# Main_Board_v3_Quad_MD.net
KiCad netlist of a schematic drawn in EAGLE
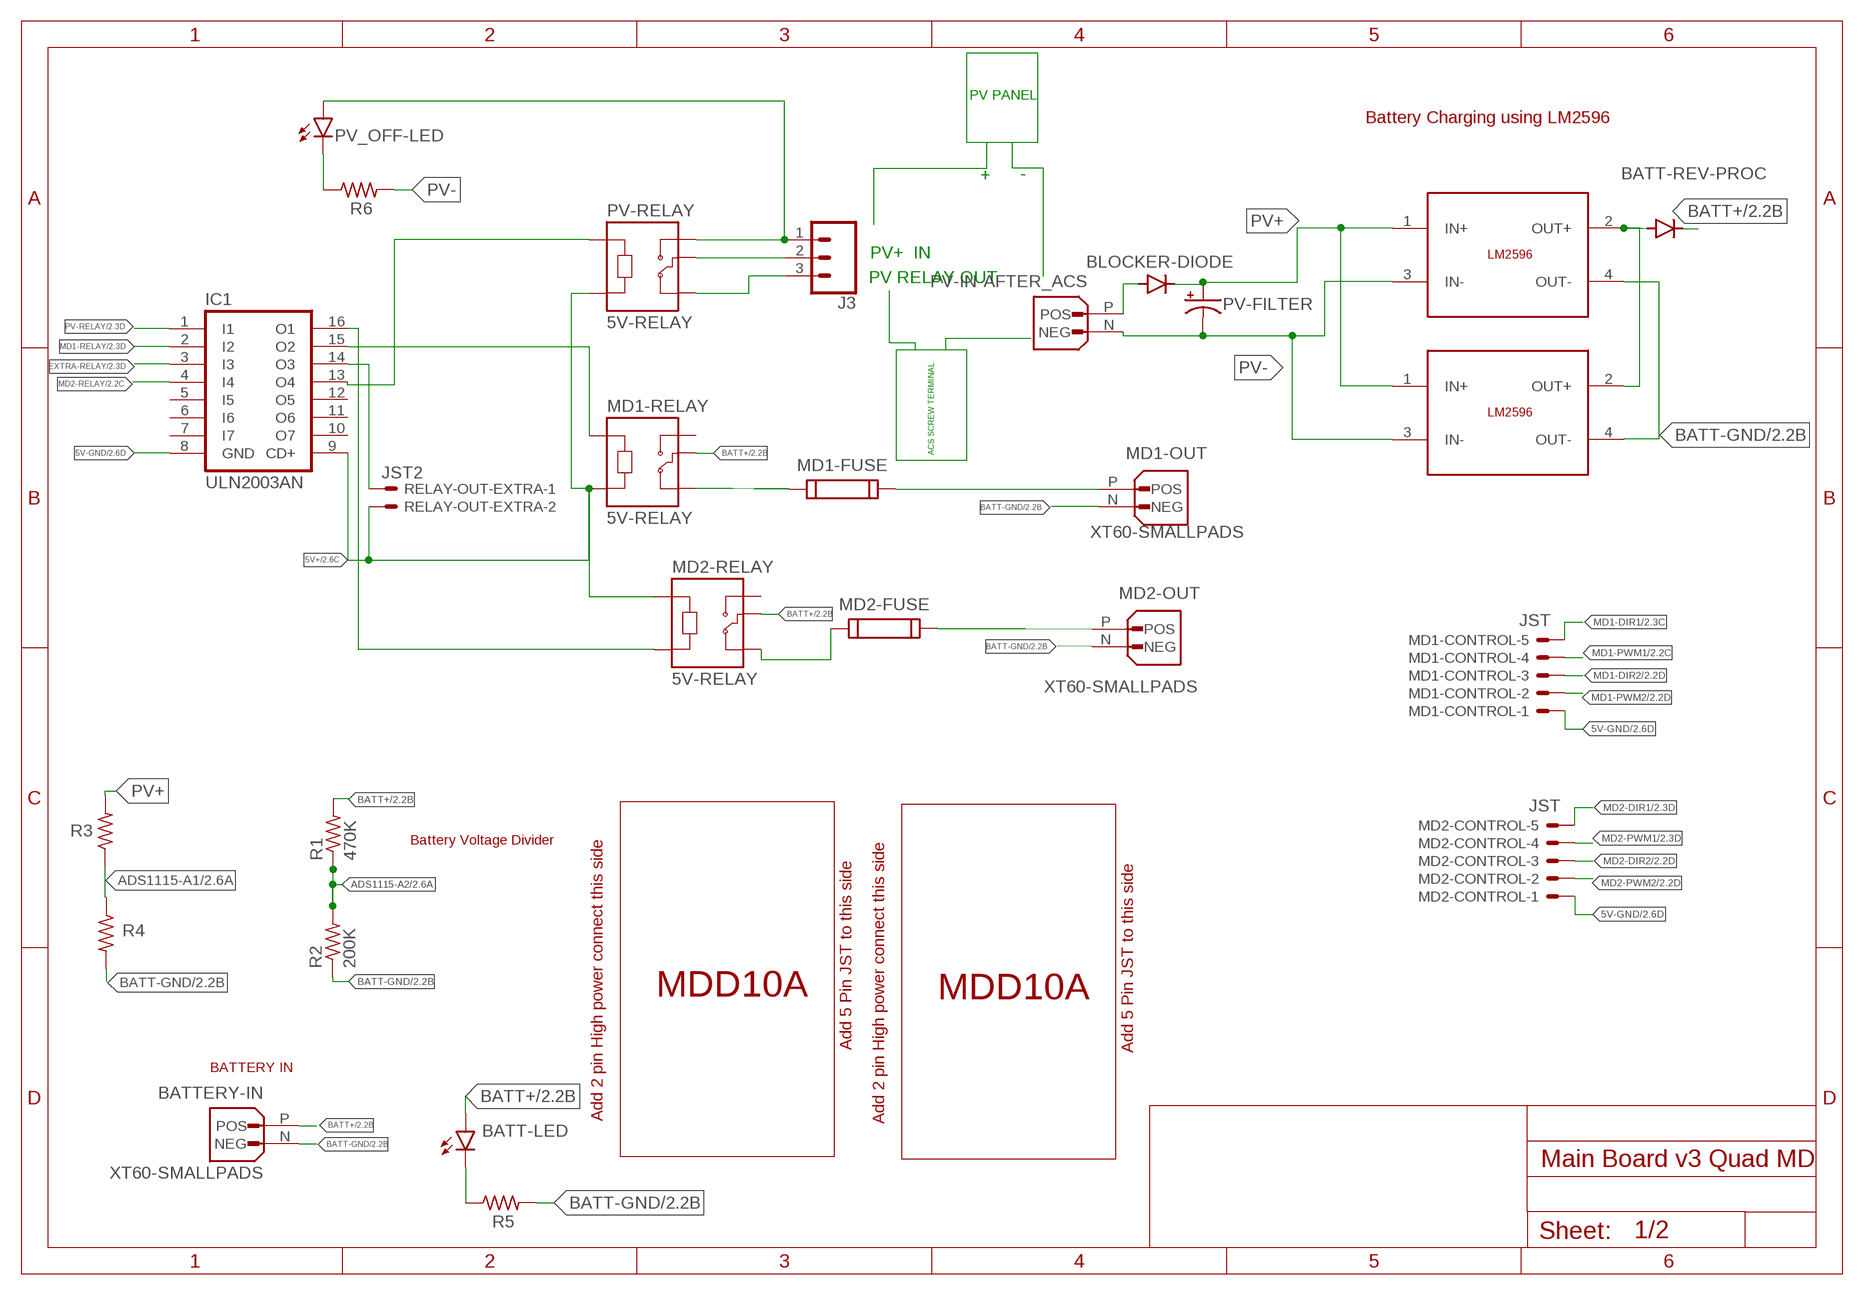
[diagram p0: schematic, sheet 1]
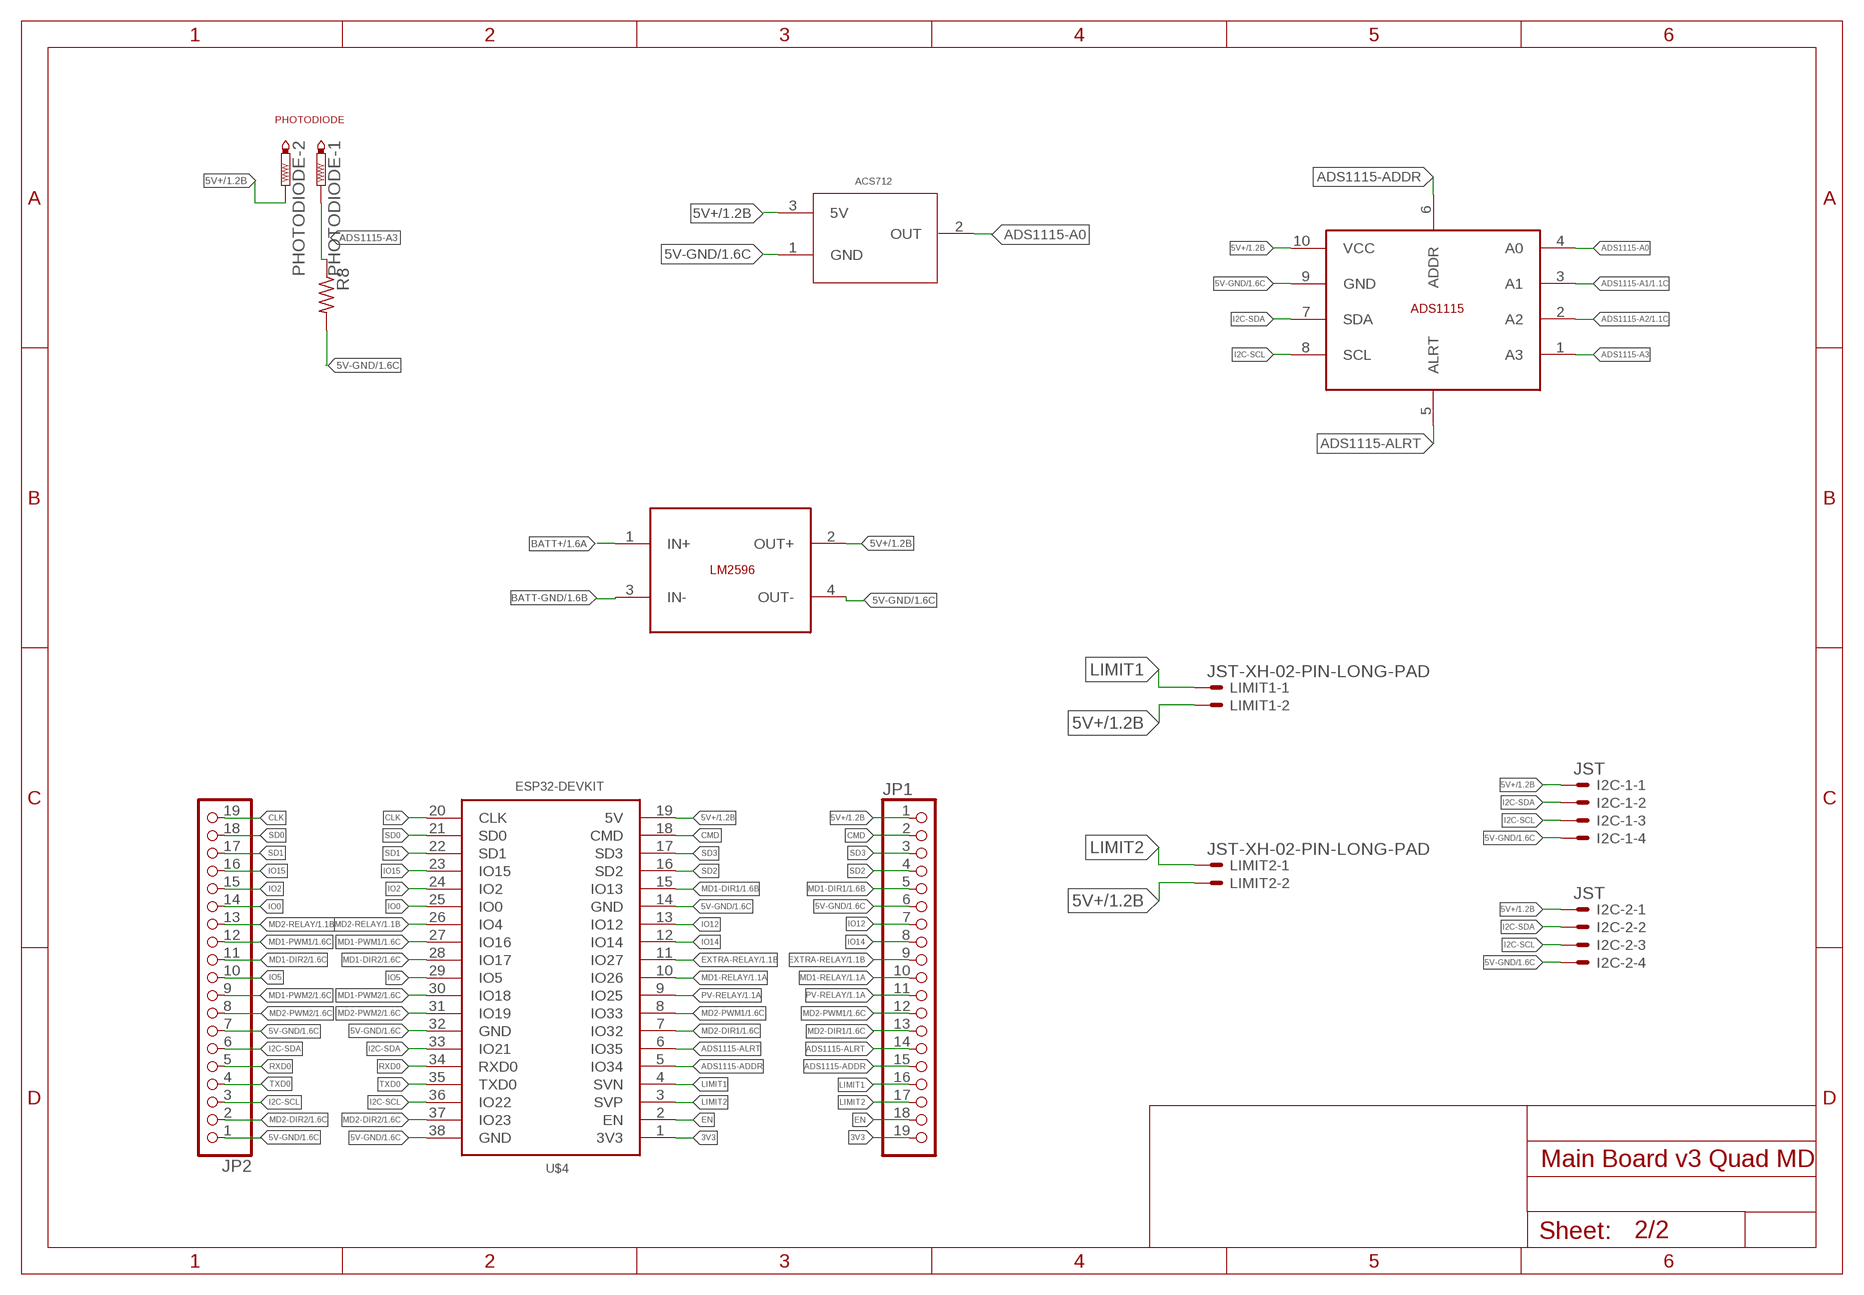
[diagram p1: schematic, sheet 2]

(export (version "E")
  (design (tool "Eeschema 10.0.6"))
  (components
    (comp (ref "BATT-LED")
      (value "SFH482")
      (footprint "eagle-import:SFH482")
      (libsource (lib "eagle-import") (part "SFH482"))
    )
    (comp (ref "BATT-REV-PROC")
      (value "1N5400")
      (footprint "eagle-import:DO201-15")
      (libsource (lib "eagle-import") (part "1N5400"))
    )
    (comp (ref "BATTERY-IN")
      (value "XT60-SMALLPADS")
      (footprint "eagle-import:XT-60-SMALLPADS")
      (libsource (lib "eagle-import") (part "XT60-SMALLPADS"))
    )
    (comp (ref "BLOCKER-DIODE")
      (value "1N5400")
      (footprint "eagle-import:DO201-15")
      (libsource (lib "eagle-import") (part "1N5400"))
    )
    (comp (ref "IC1")
      (value "ULN2003AN")
      (footprint "eagle-import:DIL16")
      (fields
        (field (name "MF") "STMicroelectronics")
        (field (name "MP") "ULN2003A")
        (field (name "SPICEPREFIX") "X")
      )
      (libsource (lib "eagle-import") (part "ULN2003AN"))
    )
    (comp (ref "J3")
      (value "CONN_03SCREW_LOCK")
      (footprint "eagle-import:SCREWTERMINAL-3.5MM-3_LOCK.007S")
      (libsource (lib "eagle-import") (part "CONN_03SCREW_LOCK"))
    )
    (comp (ref "MD1-CONTROL")
      (value "JST")
      (footprint "eagle-import:JST-XH-05-PACKAGE-LONG-PAD")
      (libsource (lib "eagle-import") (part "JST-XH-05-PIN-LONG-PAD"))
    )
    (comp (ref "MD1-FUSE")
      (value "696101000002")
      (footprint "eagle-import:696101000002")
      (libsource (lib "eagle-import") (part "696101000002"))
    )
    (comp (ref "MD1-OUT")
      (value "XT60-SMALLPADS")
      (footprint "eagle-import:XT-60-SMALLPADS")
      (libsource (lib "eagle-import") (part "XT60-SMALLPADS"))
    )
    (comp (ref "MD1-RELAY")
      (value "5V-RELAY")
      (footprint "eagle-import:RELAY-SRD-05VDC-SL-C")
      (fields (field (name "MF") "Songle Relay") (field (name "MP") "SRD-05VDC-SL-C"))
      (libsource (lib "eagle-import") (part "5V-RELAY"))
    )
    (comp (ref "MD2-CONTROL")
      (value "JST")
      (footprint "eagle-import:JST-XH-05-PACKAGE-LONG-PAD")
      (libsource (lib "eagle-import") (part "JST-XH-05-PIN-LONG-PAD"))
    )
    (comp (ref "MD2-FUSE")
      (value "696101000002")
      (footprint "eagle-import:696101000002")
      (libsource (lib "eagle-import") (part "696101000002"))
    )
    (comp (ref "MD2-OUT")
      (value "XT60-SMALLPADS")
      (footprint "eagle-import:XT-60-SMALLPADS")
      (libsource (lib "eagle-import") (part "XT60-SMALLPADS"))
    )
    (comp (ref "MD2-RELAY")
      (value "5V-RELAY")
      (footprint "eagle-import:RELAY-SRD-05VDC-SL-C")
      (fields (field (name "MF") "Songle Relay") (field (name "MP") "SRD-05VDC-SL-C"))
      (libsource (lib "eagle-import") (part "5V-RELAY"))
    )
    (comp (ref "PV-FILTER")
      (value "CPOL-USE5-6")
      (footprint "eagle-import:E5-6")
      (libsource (lib "eagle-import") (part "CPOL-USE5-6"))
    )
    (comp (ref "PV-IN-AFTER_ACS")
      (value "XT60-SMALLPADS")
      (footprint "eagle-import:XT-60-SMALLPADS")
      (libsource (lib "eagle-import") (part "XT60-SMALLPADS"))
    )
    (comp (ref "PV-RELAY")
      (value "5V-RELAY")
      (footprint "eagle-import:RELAY-SRD-05VDC-SL-C")
      (fields (field (name "MF") "Songle Relay") (field (name "MP") "SRD-05VDC-SL-C"))
      (libsource (lib "eagle-import") (part "5V-RELAY"))
    )
    (comp (ref "PV_OFF-LED")
      (value "SFH482")
      (footprint "eagle-import:SFH482")
      (libsource (lib "eagle-import") (part "SFH482"))
    )
    (comp (ref "R1")
      (value "470K")
      (footprint "eagle-import:0309_12")
      (libsource (lib "eagle-import") (part "R-US_0309/12"))
    )
    (comp (ref "R2")
      (value "200K")
      (footprint "eagle-import:0309_12")
      (libsource (lib "eagle-import") (part "R-US_0309/12"))
    )
    (comp (ref "R3")
      (value "R-US_0309/12")
      (footprint "eagle-import:0309_12")
      (libsource (lib "eagle-import") (part "R-US_0309/12"))
    )
    (comp (ref "R4")
      (value "R-US_0309/12")
      (footprint "eagle-import:0309_12")
      (libsource (lib "eagle-import") (part "R-US_0309/12"))
    )
    (comp (ref "R5")
      (value "R-US_0309/12")
      (footprint "eagle-import:0309_12")
      (libsource (lib "eagle-import") (part "R-US_0309/12"))
    )
    (comp (ref "R6")
      (value "R-US_0309/12")
      (footprint "eagle-import:0309_12")
      (libsource (lib "eagle-import") (part "R-US_0309/12"))
    )
    (comp (ref "RELAY-OUT-EXTRA")
      (value "JST2")
      (footprint "eagle-import:JST-XH-02-PACKAGE-LONG-PAD")
      (libsource (lib "eagle-import") (part "JST-XH-02-PIN-LONG-PAD"))
    )
    (comp (ref "U$1")
      (value "LM2596-MODULE")
      (footprint "eagle-import:LM2596-MODULE")
      (libsource (lib "eagle-import") (part "LM2596-MODULE"))
    )
    (comp (ref "U$2")
      (value "LM2596-MODULE")
      (footprint "eagle-import:LM2596-MODULE")
      (libsource (lib "eagle-import") (part "LM2596-MODULE"))
    )
    (comp (ref "U$3")
      (value "MDD10A-MODULE")
      (footprint "eagle-import:MDD10A")
      (libsource (lib "eagle-import") (part "MDD10A-MODULE"))
    )
    (comp (ref "U$7")
      (value "MDD10A-MODULE")
      (footprint "eagle-import:MDD10A")
      (libsource (lib "eagle-import") (part "MDD10A-MODULE"))
    )
    (comp (ref "I2C-1")
      (value "JST")
      (footprint "eagle-import:JST-XH-04-PACKAGE-LONG-PAD")
      (libsource (lib "eagle-import") (part "JST-XH-04-PIN-LONG-PAD"))
    )
    (comp (ref "I2C-2")
      (value "JST")
      (footprint "eagle-import:JST-XH-04-PACKAGE-LONG-PAD")
      (libsource (lib "eagle-import") (part "JST-XH-04-PIN-LONG-PAD"))
    )
    (comp (ref "JP1")
      (value "PINHD-1X19")
      (footprint "eagle-import:1X19")
      (libsource (lib "eagle-import") (part "PINHD-1X19"))
    )
    (comp (ref "JP2")
      (value "PINHD-1X19")
      (footprint "eagle-import:1X19")
      (libsource (lib "eagle-import") (part "PINHD-1X19"))
    )
    (comp (ref "LIMIT1")
      (value "JST-XH-02-PIN-LONG-PAD")
      (footprint "eagle-import:JST-XH-02-PACKAGE-LONG-PAD")
      (libsource (lib "eagle-import") (part "JST-XH-02-PIN-LONG-PAD"))
    )
    (comp (ref "LIMIT2")
      (value "JST-XH-02-PIN-LONG-PAD")
      (footprint "eagle-import:JST-XH-02-PACKAGE-LONG-PAD")
      (libsource (lib "eagle-import") (part "JST-XH-02-PIN-LONG-PAD"))
    )
    (comp (ref "PHOTODIODE")
      (value "PTR2")
      (footprint "eagle-import:P2-38-17")
      (libsource (lib "eagle-import") (part "PTR2"))
    )
    (comp (ref "R8")
      (value "R-US_0309/12")
      (footprint "eagle-import:0309_12")
      (libsource (lib "eagle-import") (part "R-US_0309/12"))
    )
    (comp (ref "U$4")
      (value "ESP32-DEVKIT")
      (footprint "eagle-import:ESP32-38PINS")
      (libsource (lib "eagle-import") (part "ESP32-DEVKIT"))
    )
    (comp (ref "U$5")
      (value "ACS712-MODULE")
      (footprint "eagle-import:ACS712-MODULE")
      (libsource (lib "eagle-import") (part "ACS712-MODULE"))
    )
    (comp (ref "U$6")
      (value "ADS1115-MODULE")
      (footprint "eagle-import:ADS1115-MODULE")
      (libsource (lib "eagle-import") (part "ADS1115-MODULE"))
    )
    (comp (ref "U$8")
      (value "LM2596-MODULE")
      (footprint "eagle-import:LM2596-MODULE")
      (libsource (lib "eagle-import") (part "LM2596-MODULE"))
    )
  )
  (nets
    (net (code "1") (name "3V3") (class "Default")
      (node (ref "JP1") (pin "19") (pinfunction "19_19") (pintype "passive"))
      (node (ref "U$4") (pin "1") (pinfunction "3V3_1") (pintype "bidirectional"))
    )
    (net (code "2") (name "5V+") (class "Default")
      (node (ref "I2C-1") (pin "1") (pinfunction "S_1") (pintype "passive"))
      (node (ref "I2C-2") (pin "1") (pinfunction "S_1") (pintype "passive"))
      (node (ref "IC1") (pin "9") (pinfunction "CD+_9") (pintype "passive"))
      (node (ref "JP1") (pin "1") (pinfunction "1_1") (pintype "passive"))
      (node (ref "LIMIT1") (pin "2") (pinfunction "S_2") (pintype "passive"))
      (node (ref "LIMIT2") (pin "2") (pinfunction "S_2") (pintype "passive"))
      (node (ref "MD1-RELAY") (pin "A2") (pinfunction "A2_A2") (pintype "passive"))
      (node (ref "MD2-RELAY") (pin "A1") (pinfunction "A1_A1") (pintype "passive"))
      (node (ref "PHOTODIODE") (pin "TP-2") (pinfunction "TP_TP-2") (pintype "input"))
      (node (ref "PV-RELAY") (pin "A2") (pinfunction "A2_A2") (pintype "passive"))
      (node (ref "RELAY-OUT-EXTRA") (pin "2") (pinfunction "S_2") (pintype "passive"))
      (node (ref "U$4") (pin "19") (pinfunction "5V_19") (pintype "bidirectional"))
      (node (ref "U$5") (pin "3") (pinfunction "5V_3") (pintype "bidirectional"))
      (node (ref "U$6") (pin "10") (pinfunction "VCC_10") (pintype "bidirectional"))
      (node (ref "U$8") (pin "2") (pinfunction "OUT+_2") (pintype "bidirectional"))
    )
    (net (code "3") (name "5V-GND") (class "Default")
      (node (ref "I2C-1") (pin "4") (pinfunction "S_4") (pintype "passive"))
      (node (ref "I2C-2") (pin "4") (pinfunction "S_4") (pintype "passive"))
      (node (ref "IC1") (pin "8") (pinfunction "GND_8") (pintype "power_in"))
      (node (ref "JP1") (pin "6") (pinfunction "6_6") (pintype "passive"))
      (node (ref "JP2") (pin "1") (pinfunction "1_1") (pintype "passive"))
      (node (ref "JP2") (pin "7") (pinfunction "7_7") (pintype "passive"))
      (node (ref "MD1-CONTROL") (pin "1") (pinfunction "S_1") (pintype "passive"))
      (node (ref "MD2-CONTROL") (pin "1") (pinfunction "S_1") (pintype "passive"))
      (node (ref "R8") (pin "2") (pinfunction "2_2") (pintype "passive"))
      (node (ref "U$4") (pin "14") (pinfunction "GND_14") (pintype "bidirectional"))
      (node (ref "U$4") (pin "32") (pinfunction "GND_32") (pintype "bidirectional"))
      (node (ref "U$4") (pin "38") (pinfunction "GND_38") (pintype "bidirectional"))
      (node (ref "U$5") (pin "1") (pinfunction "GND_1") (pintype "bidirectional"))
      (node (ref "U$6") (pin "9") (pinfunction "GND_9") (pintype "bidirectional"))
      (node (ref "U$8") (pin "4") (pinfunction "OUT-_4") (pintype "bidirectional"))
    )
    (net (code "4") (name "ADS1115-A0") (class "Default")
      (node (ref "U$5") (pin "2") (pinfunction "OUT_2") (pintype "bidirectional"))
      (node (ref "U$6") (pin "4") (pinfunction "A0_4") (pintype "bidirectional"))
    )
    (net (code "5") (name "ADS1115-A1") (class "Default")
      (node (ref "R3") (pin "1") (pinfunction "1_1") (pintype "passive"))
      (node (ref "R4") (pin "1") (pinfunction "1_1") (pintype "passive"))
      (node (ref "U$6") (pin "3") (pinfunction "A1_3") (pintype "bidirectional"))
    )
    (net (code "6") (name "ADS1115-A2") (class "Default")
      (node (ref "R1") (pin "1") (pinfunction "1_1") (pintype "passive"))
      (node (ref "R2") (pin "2") (pinfunction "2_2") (pintype "passive"))
      (node (ref "U$6") (pin "2") (pinfunction "A2_2") (pintype "bidirectional"))
    )
    (net (code "7") (name "ADS1115-A3") (class "Default")
      (node (ref "PHOTODIODE") (pin "TP-1") (pinfunction "TP_TP-1") (pintype "input"))
      (node (ref "R8") (pin "1") (pinfunction "1_1") (pintype "passive"))
      (node (ref "U$6") (pin "1") (pinfunction "A3_1") (pintype "bidirectional"))
    )
    (net (code "8") (name "ADS1115-ADDR") (class "Default")
      (node (ref "JP1") (pin "15") (pinfunction "15_15") (pintype "passive"))
      (node (ref "U$4") (pin "5") (pinfunction "IO34_5") (pintype "bidirectional"))
      (node (ref "U$6") (pin "6") (pinfunction "ADDR_6") (pintype "bidirectional"))
    )
    (net (code "9") (name "ADS1115-ALRT") (class "Default")
      (node (ref "JP1") (pin "14") (pinfunction "14_14") (pintype "passive"))
      (node (ref "U$4") (pin "6") (pinfunction "IO35_6") (pintype "bidirectional"))
      (node (ref "U$6") (pin "5") (pinfunction "ALRT_5") (pintype "bidirectional"))
    )
    (net (code "10") (name "BATT+") (class "Default")
      (node (ref "BATT-LED") (pin "A") (pinfunction "A_A") (pintype "passive"))
      (node (ref "BATT-REV-PROC") (pin "C") (pinfunction "C_C") (pintype "passive"))
      (node (ref "BATTERY-IN") (pin "P") (pinfunction "POS_P") (pintype "passive"))
      (node (ref "MD1-RELAY") (pin "COM") (pinfunction "COM_COM") (pintype "passive"))
      (node (ref "MD2-RELAY") (pin "COM") (pinfunction "COM_COM") (pintype "passive"))
      (node (ref "R1") (pin "2") (pinfunction "2_2") (pintype "passive"))
      (node (ref "U$8") (pin "1") (pinfunction "IN+_1") (pintype "bidirectional"))
    )
    (net (code "11") (name "BATT-GND") (class "Default")
      (node (ref "BATTERY-IN") (pin "N") (pinfunction "NEG_N") (pintype "passive"))
      (node (ref "MD1-OUT") (pin "N") (pinfunction "NEG_N") (pintype "passive"))
      (node (ref "MD2-OUT") (pin "N") (pinfunction "NEG_N") (pintype "passive"))
      (node (ref "R2") (pin "1") (pinfunction "1_1") (pintype "passive"))
      (node (ref "R4") (pin "2") (pinfunction "2_2") (pintype "passive"))
      (node (ref "R5") (pin "2") (pinfunction "2_2") (pintype "passive"))
      (node (ref "U$1") (pin "4") (pinfunction "OUT-_4") (pintype "bidirectional"))
      (node (ref "U$2") (pin "4") (pinfunction "OUT-_4") (pintype "bidirectional"))
      (node (ref "U$8") (pin "3") (pinfunction "IN-_3") (pintype "bidirectional"))
    )
    (net (code "12") (name "CLK") (class "Default")
      (node (ref "JP2") (pin "19") (pinfunction "19_19") (pintype "passive"))
      (node (ref "U$4") (pin "20") (pinfunction "CLK_20") (pintype "bidirectional"))
    )
    (net (code "13") (name "CMD") (class "Default")
      (node (ref "JP1") (pin "2") (pinfunction "2_2") (pintype "passive"))
      (node (ref "U$4") (pin "18") (pinfunction "CMD_18") (pintype "bidirectional"))
    )
    (net (code "14") (name "EN") (class "Default")
      (node (ref "JP1") (pin "18") (pinfunction "18_18") (pintype "passive"))
      (node (ref "U$4") (pin "2") (pinfunction "EN_2") (pintype "bidirectional"))
    )
    (net (code "15") (name "EXTRA-RELAY") (class "Default")
      (node (ref "IC1") (pin "3") (pinfunction "I3_3") (pintype "input"))
      (node (ref "JP1") (pin "9") (pinfunction "9_9") (pintype "passive"))
      (node (ref "U$4") (pin "11") (pinfunction "IO27_11") (pintype "bidirectional"))
    )
    (net (code "16") (name "I2C-SCL") (class "Default")
      (node (ref "I2C-1") (pin "3") (pinfunction "S_3") (pintype "passive"))
      (node (ref "I2C-2") (pin "3") (pinfunction "S_3") (pintype "passive"))
      (node (ref "JP2") (pin "3") (pinfunction "3_3") (pintype "passive"))
      (node (ref "U$4") (pin "36") (pinfunction "IO22_36") (pintype "bidirectional"))
      (node (ref "U$6") (pin "8") (pinfunction "SCL_8") (pintype "bidirectional"))
    )
    (net (code "17") (name "I2C-SDA") (class "Default")
      (node (ref "I2C-1") (pin "2") (pinfunction "S_2") (pintype "passive"))
      (node (ref "I2C-2") (pin "2") (pinfunction "S_2") (pintype "passive"))
      (node (ref "JP2") (pin "6") (pinfunction "6_6") (pintype "passive"))
      (node (ref "U$4") (pin "33") (pinfunction "IO21_33") (pintype "bidirectional"))
      (node (ref "U$6") (pin "7") (pinfunction "SDA_7") (pintype "bidirectional"))
    )
    (net (code "18") (name "IO0") (class "Default")
      (node (ref "JP2") (pin "14") (pinfunction "14_14") (pintype "passive"))
      (node (ref "U$4") (pin "25") (pinfunction "IO0_25") (pintype "bidirectional"))
    )
    (net (code "19") (name "IO2") (class "Default")
      (node (ref "JP2") (pin "15") (pinfunction "15_15") (pintype "passive"))
      (node (ref "U$4") (pin "24") (pinfunction "IO2_24") (pintype "bidirectional"))
    )
    (net (code "20") (name "IO5") (class "Default")
      (node (ref "JP2") (pin "10") (pinfunction "10_10") (pintype "passive"))
      (node (ref "U$4") (pin "29") (pinfunction "IO5_29") (pintype "bidirectional"))
    )
    (net (code "21") (name "IO12") (class "Default")
      (node (ref "JP1") (pin "7") (pinfunction "7_7") (pintype "passive"))
      (node (ref "U$4") (pin "13") (pinfunction "IO12_13") (pintype "bidirectional"))
    )
    (net (code "22") (name "IO14") (class "Default")
      (node (ref "JP1") (pin "8") (pinfunction "8_8") (pintype "passive"))
      (node (ref "U$4") (pin "12") (pinfunction "IO14_12") (pintype "bidirectional"))
    )
    (net (code "23") (name "IO15") (class "Default")
      (node (ref "JP2") (pin "16") (pinfunction "16_16") (pintype "passive"))
      (node (ref "U$4") (pin "23") (pinfunction "IO15_23") (pintype "bidirectional"))
    )
    (net (code "24") (name "LIMIT1") (class "Default")
      (node (ref "JP1") (pin "16") (pinfunction "16_16") (pintype "passive"))
      (node (ref "LIMIT1") (pin "1") (pinfunction "S_1") (pintype "passive"))
      (node (ref "U$4") (pin "4") (pinfunction "SVN_4") (pintype "bidirectional"))
    )
    (net (code "25") (name "LIMIT2") (class "Default")
      (node (ref "JP1") (pin "17") (pinfunction "17_17") (pintype "passive"))
      (node (ref "LIMIT2") (pin "1") (pinfunction "S_1") (pintype "passive"))
      (node (ref "U$4") (pin "3") (pinfunction "SVP_3") (pintype "bidirectional"))
    )
    (net (code "26") (name "MD1-DIR1") (class "Default")
      (node (ref "JP1") (pin "5") (pinfunction "5_5") (pintype "passive"))
      (node (ref "MD1-CONTROL") (pin "5") (pinfunction "S_5") (pintype "passive"))
      (node (ref "U$4") (pin "15") (pinfunction "IO13_15") (pintype "bidirectional"))
    )
    (net (code "27") (name "MD1-DIR2") (class "Default")
      (node (ref "JP2") (pin "11") (pinfunction "11_11") (pintype "passive"))
      (node (ref "MD1-CONTROL") (pin "3") (pinfunction "S_3") (pintype "passive"))
      (node (ref "U$4") (pin "28") (pinfunction "IO17_28") (pintype "bidirectional"))
    )
    (net (code "28") (name "MD1-PWM1") (class "Default")
      (node (ref "JP2") (pin "12") (pinfunction "12_12") (pintype "passive"))
      (node (ref "MD1-CONTROL") (pin "4") (pinfunction "S_4") (pintype "passive"))
      (node (ref "U$4") (pin "27") (pinfunction "IO16_27") (pintype "bidirectional"))
    )
    (net (code "29") (name "MD1-PWM2") (class "Default")
      (node (ref "JP2") (pin "9") (pinfunction "9_9") (pintype "passive"))
      (node (ref "MD1-CONTROL") (pin "2") (pinfunction "S_2") (pintype "passive"))
      (node (ref "U$4") (pin "30") (pinfunction "IO18_30") (pintype "bidirectional"))
    )
    (net (code "30") (name "MD1-RELAY") (class "Default")
      (node (ref "IC1") (pin "2") (pinfunction "I2_2") (pintype "input"))
      (node (ref "JP1") (pin "10") (pinfunction "10_10") (pintype "passive"))
      (node (ref "U$4") (pin "10") (pinfunction "IO26_10") (pintype "bidirectional"))
    )
    (net (code "31") (name "MD2-DIR1") (class "Default")
      (node (ref "JP1") (pin "13") (pinfunction "13_13") (pintype "passive"))
      (node (ref "MD2-CONTROL") (pin "5") (pinfunction "S_5") (pintype "passive"))
      (node (ref "U$4") (pin "7") (pinfunction "IO32_7") (pintype "bidirectional"))
    )
    (net (code "32") (name "MD2-DIR2") (class "Default")
      (node (ref "JP2") (pin "2") (pinfunction "2_2") (pintype "passive"))
      (node (ref "MD2-CONTROL") (pin "3") (pinfunction "S_3") (pintype "passive"))
      (node (ref "U$4") (pin "37") (pinfunction "IO23_37") (pintype "bidirectional"))
    )
    (net (code "33") (name "MD2-PWM1") (class "Default")
      (node (ref "JP1") (pin "12") (pinfunction "12_12") (pintype "passive"))
      (node (ref "MD2-CONTROL") (pin "4") (pinfunction "S_4") (pintype "passive"))
      (node (ref "U$4") (pin "8") (pinfunction "IO33_8") (pintype "bidirectional"))
    )
    (net (code "34") (name "MD2-PWM2") (class "Default")
      (node (ref "JP2") (pin "8") (pinfunction "8_8") (pintype "passive"))
      (node (ref "MD2-CONTROL") (pin "2") (pinfunction "S_2") (pintype "passive"))
      (node (ref "U$4") (pin "31") (pinfunction "IO19_31") (pintype "bidirectional"))
    )
    (net (code "35") (name "MD2-RELAY") (class "Default")
      (node (ref "IC1") (pin "4") (pinfunction "I4_4") (pintype "input"))
      (node (ref "JP2") (pin "13") (pinfunction "13_13") (pintype "passive"))
      (node (ref "U$4") (pin "26") (pinfunction "IO4_26") (pintype "bidirectional"))
    )
    (net (code "36") (name "Net-(BATT-LED-C)") (class "Default")
      (node (ref "BATT-LED") (pin "K") (pinfunction "C_K") (pintype "passive"))
      (node (ref "R5") (pin "1") (pinfunction "1_1") (pintype "passive"))
    )
    (net (code "37") (name "Net-(IC1-O1)") (class "Default")
      (node (ref "IC1") (pin "16") (pinfunction "O1_16") (pintype "open_collector"))
      (node (ref "MD2-RELAY") (pin "A2") (pinfunction "A2_A2") (pintype "passive"))
    )
    (net (code "38") (name "Net-(IC1-O2)") (class "Default")
      (node (ref "IC1") (pin "15") (pinfunction "O2_15") (pintype "open_collector"))
      (node (ref "MD1-RELAY") (pin "A1") (pinfunction "A1_A1") (pintype "passive"))
    )
    (net (code "39") (name "Net-(IC1-O3)") (class "Default")
      (node (ref "IC1") (pin "14") (pinfunction "O3_14") (pintype "open_collector"))
      (node (ref "RELAY-OUT-EXTRA") (pin "1") (pinfunction "S_1") (pintype "passive"))
    )
    (net (code "40") (name "Net-(IC1-O4)") (class "Default")
      (node (ref "IC1") (pin "13") (pinfunction "O4_13") (pintype "open_collector"))
      (node (ref "PV-RELAY") (pin "A1") (pinfunction "A1_A1") (pintype "passive"))
    )
    (net (code "41") (name "Net-(J3-Pad1)") (class "Default")
      (node (ref "J3") (pin "1") (pinfunction "1_1") (pintype "passive"))
      (node (ref "PV-RELAY") (pin "NO") (pinfunction "NO_NO") (pintype "passive"))
      (node (ref "PV_OFF-LED") (pin "A") (pinfunction "A_A") (pintype "passive"))
    )
    (net (code "42") (name "Net-(J3-Pad2)") (class "Default")
      (node (ref "J3") (pin "2") (pinfunction "2_2") (pintype "passive"))
      (node (ref "PV-RELAY") (pin "COM") (pinfunction "COM_COM") (pintype "passive"))
    )
    (net (code "43") (name "Net-(J3-Pad3)") (class "Default")
      (node (ref "J3") (pin "3") (pinfunction "3_3") (pintype "passive"))
      (node (ref "PV-RELAY") (pin "NC") (pinfunction "NC_NC") (pintype "passive"))
    )
    (net (code "44") (name "Net-(MD1-FUSE-Pad1)") (class "Default")
      (node (ref "MD1-FUSE") (pin "1") (pinfunction "1_1") (pintype "passive"))
      (node (ref "MD1-RELAY") (pin "NC") (pinfunction "NC_NC") (pintype "passive"))
    )
    (net (code "45") (name "Net-(MD1-OUT-POS)") (class "Default")
      (node (ref "MD1-FUSE") (pin "2") (pinfunction "2_2") (pintype "passive"))
      (node (ref "MD1-OUT") (pin "P") (pinfunction "POS_P") (pintype "passive"))
    )
    (net (code "46") (name "Net-(MD2-FUSE-Pad1)") (class "Default")
      (node (ref "MD2-FUSE") (pin "1") (pinfunction "1_1") (pintype "passive"))
      (node (ref "MD2-RELAY") (pin "NC") (pinfunction "NC_NC") (pintype "passive"))
    )
    (net (code "47") (name "Net-(MD2-OUT-POS)") (class "Default")
      (node (ref "MD2-FUSE") (pin "2") (pinfunction "2_2") (pintype "passive"))
      (node (ref "MD2-OUT") (pin "P") (pinfunction "POS_P") (pintype "passive"))
    )
    (net (code "48") (name "Net-(PV-IN-AFTER_ACS-POS)") (class "Default")
      (node (ref "BLOCKER-DIODE") (pin "A") (pinfunction "A_A") (pintype "passive"))
      (node (ref "PV-IN-AFTER_ACS") (pin "P") (pinfunction "POS_P") (pintype "passive"))
    )
    (net (code "49") (name "Net-(PV_OFF-LED-C)") (class "Default")
      (node (ref "PV_OFF-LED") (pin "K") (pinfunction "C_K") (pintype "passive"))
      (node (ref "R6") (pin "1") (pinfunction "1_1") (pintype "passive"))
    )
    (net (code "50") (name "Net-(U$1-OUT+)") (class "Default")
      (node (ref "BATT-REV-PROC") (pin "A") (pinfunction "A_A") (pintype "passive"))
      (node (ref "U$1") (pin "2") (pinfunction "OUT+_2") (pintype "bidirectional"))
      (node (ref "U$2") (pin "2") (pinfunction "OUT+_2") (pintype "bidirectional"))
    )
    (net (code "51") (name "PV+") (class "Default")
      (node (ref "BLOCKER-DIODE") (pin "C") (pinfunction "C_C") (pintype "passive"))
      (node (ref "PV-FILTER") (pin "+") (pinfunction "+_+") (pintype "passive"))
      (node (ref "R3") (pin "2") (pinfunction "2_2") (pintype "passive"))
      (node (ref "U$1") (pin "1") (pinfunction "IN+_1") (pintype "bidirectional"))
      (node (ref "U$2") (pin "1") (pinfunction "IN+_1") (pintype "bidirectional"))
    )
    (net (code "52") (name "PV-") (class "Default")
      (node (ref "PV-FILTER") (pin "-") (pinfunction "-_-") (pintype "passive"))
      (node (ref "PV-IN-AFTER_ACS") (pin "N") (pinfunction "NEG_N") (pintype "passive"))
      (node (ref "R6") (pin "2") (pinfunction "2_2") (pintype "passive"))
      (node (ref "U$1") (pin "3") (pinfunction "IN-_3") (pintype "bidirectional"))
      (node (ref "U$2") (pin "3") (pinfunction "IN-_3") (pintype "bidirectional"))
    )
    (net (code "53") (name "PV-RELAY") (class "Default")
      (node (ref "IC1") (pin "1") (pinfunction "I1_1") (pintype "input"))
      (node (ref "JP1") (pin "11") (pinfunction "11_11") (pintype "passive"))
      (node (ref "U$4") (pin "9") (pinfunction "IO25_9") (pintype "bidirectional"))
    )
    (net (code "54") (name "RXD0") (class "Default")
      (node (ref "JP2") (pin "5") (pinfunction "5_5") (pintype "passive"))
      (node (ref "U$4") (pin "34") (pinfunction "RXD0_34") (pintype "bidirectional"))
    )
    (net (code "55") (name "SD0") (class "Default")
      (node (ref "JP2") (pin "18") (pinfunction "18_18") (pintype "passive"))
      (node (ref "U$4") (pin "21") (pinfunction "SD0_21") (pintype "bidirectional"))
    )
    (net (code "56") (name "SD1") (class "Default")
      (node (ref "JP2") (pin "17") (pinfunction "17_17") (pintype "passive"))
      (node (ref "U$4") (pin "22") (pinfunction "SD1_22") (pintype "bidirectional"))
    )
    (net (code "57") (name "SD2") (class "Default")
      (node (ref "JP1") (pin "4") (pinfunction "4_4") (pintype "passive"))
      (node (ref "U$4") (pin "16") (pinfunction "SD2_16") (pintype "bidirectional"))
    )
    (net (code "58") (name "SD3") (class "Default")
      (node (ref "JP1") (pin "3") (pinfunction "3_3") (pintype "passive"))
      (node (ref "U$4") (pin "17") (pinfunction "SD3_17") (pintype "bidirectional"))
    )
    (net (code "59") (name "TXD0") (class "Default")
      (node (ref "JP2") (pin "4") (pinfunction "4_4") (pintype "passive"))
      (node (ref "U$4") (pin "35") (pinfunction "TXD0_35") (pintype "bidirectional"))
    )
    (net (code "60") (name "unconnected-(IC1-I5-Pad5)") (class "Default")
      (node (ref "IC1") (pin "5") (pinfunction "I5_5") (pintype "input"))
    )
    (net (code "61") (name "unconnected-(IC1-I6-Pad6)") (class "Default")
      (node (ref "IC1") (pin "6") (pinfunction "I6_6") (pintype "input"))
    )
    (net (code "62") (name "unconnected-(IC1-I7-Pad7)") (class "Default")
      (node (ref "IC1") (pin "7") (pinfunction "I7_7") (pintype "input"))
    )
    (net (code "63") (name "unconnected-(IC1-O5-Pad12)") (class "Default")
      (node (ref "IC1") (pin "12") (pinfunction "O5_12") (pintype "open_collector"))
    )
    (net (code "64") (name "unconnected-(IC1-O6-Pad11)") (class "Default")
      (node (ref "IC1") (pin "11") (pinfunction "O6_11") (pintype "open_collector"))
    )
    (net (code "65") (name "unconnected-(IC1-O7-Pad10)") (class "Default")
      (node (ref "IC1") (pin "10") (pinfunction "O7_10") (pintype "open_collector"))
    )
    (net (code "66") (name "unconnected-(MD1-RELAY-PadNO)") (class "Default")
      (node (ref "MD1-RELAY") (pin "NO") (pinfunction "NO_NO") (pintype "passive"))
    )
    (net (code "67") (name "unconnected-(MD2-RELAY-PadNO)") (class "Default")
      (node (ref "MD2-RELAY") (pin "NO") (pinfunction "NO_NO") (pintype "passive"))
    )
  )
)
